# PM12_LDO.net
KiCad netlist of a schematic drawn in Altium Designer
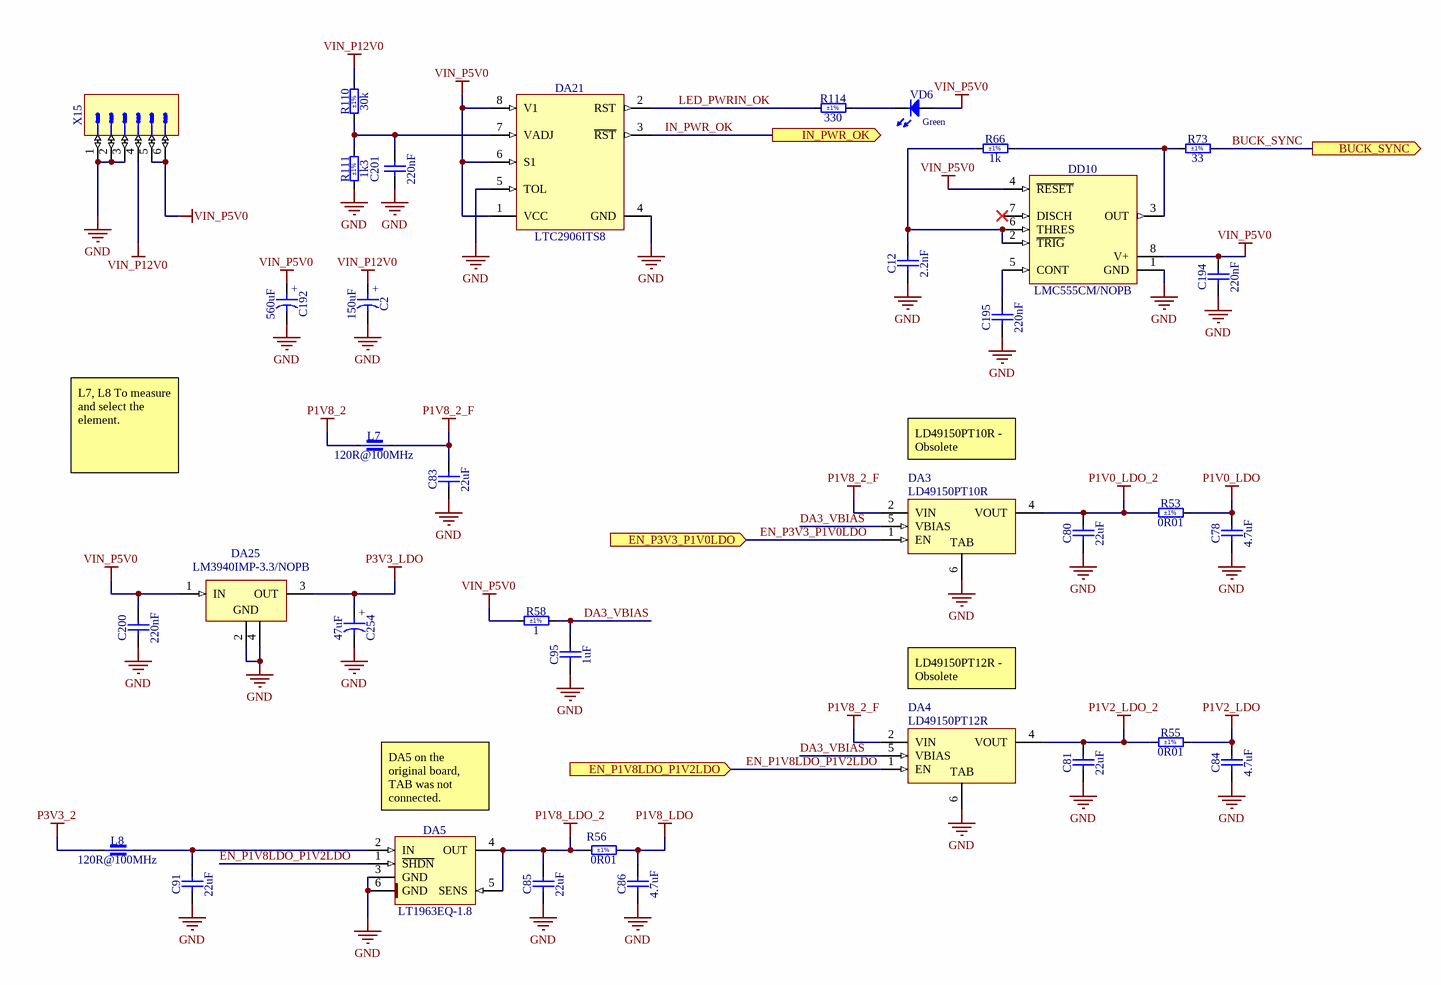
[diagram p0: PM12_LDO.SchDoc]

(export (version "E")
  (design (tool "Eeschema 10.0.6"))
  (components
    (comp (ref "C2")
      (value "150uF")
      (footprint "CAPAE830X1020N")
      (description "Polarised capacitor")
      (fields
        (field (name "PART NUMBER") "CAE830-1020_150UF_25V_20%")
        (field (name "VOLTAGE") "25V")
        (field (name "AUTHOR") "CERN DEM HF")
      )
      (libsource (lib "Capacitors") (part "Capacitor - polarized"))
    )
    (comp (ref "C12")
      (value "2.2nF")
      (footprint "CAPC2013X100N")
      (description "Non-polarised capacitor")
      (fields
        (field (name "PART NUMBER") "CC0805_2.2NF_50V_5%_C0G")
        (field (name "VOLTAGE") "50V")
        (field (name "AUTHOR") "CERN DEM MR")
      )
      (libsource (lib "Capacitors") (part "Capacitor - non polarized"))
    )
    (comp (ref "C78")
      (value "4.7uF")
      (footprint "CAPC2012X145N")
      (description "Non-polarised capacitor")
      (fields
        (field (name "PART NUMBER") "CC0805_4.7UF_50V_10%_X7R")
        (field (name "VOLTAGE") "50V")
        (field (name "AUTHOR") "CERN DEM JMW")
      )
      (libsource (lib "Capacitors") (part "Capacitor - non polarized"))
    )
    (comp (ref "C80")
      (value "22uF")
      (footprint "CAPC3216X180N")
      (description "Non-polarised capacitor")
      (fields
        (field (name "PART NUMBER") "CC1206_22UF_25V_20%_X5R")
        (field (name "VOLTAGE") "25V")
        (field (name "AUTHOR") "CERN DEM WB")
      )
      (libsource (lib "Capacitors") (part "Capacitor - non polarized"))
    )
    (comp (ref "C81")
      (value "22uF")
      (footprint "CAPC3216X180N")
      (description "Non-polarised capacitor")
      (fields
        (field (name "PART NUMBER") "CC1206_22UF_25V_20%_X5R")
        (field (name "VOLTAGE") "25V")
        (field (name "AUTHOR") "CERN DEM WB")
      )
      (libsource (lib "Capacitors") (part "Capacitor - non polarized"))
    )
    (comp (ref "C83")
      (value "22uF")
      (footprint "CAPC3216X180N")
      (description "Non-polarised capacitor")
      (fields
        (field (name "PART NUMBER") "CC1206_22UF_25V_20%_X5R")
        (field (name "VOLTAGE") "25V")
        (field (name "AUTHOR") "CERN DEM WB")
      )
      (libsource (lib "Capacitors") (part "Capacitor - non polarized"))
    )
    (comp (ref "C84")
      (value "4.7uF")
      (footprint "CAPC2012X145N")
      (description "Non-polarised capacitor")
      (fields
        (field (name "PART NUMBER") "CC0805_4.7UF_50V_10%_X7R")
        (field (name "VOLTAGE") "50V")
        (field (name "AUTHOR") "CERN DEM JMW")
      )
      (libsource (lib "Capacitors") (part "Capacitor - non polarized"))
    )
    (comp (ref "C85")
      (value "22uF")
      (footprint "CAPC3216X180N")
      (description "Non-polarised capacitor")
      (fields
        (field (name "PART NUMBER") "CC1206_22UF_25V_20%_X5R")
        (field (name "VOLTAGE") "25V")
        (field (name "AUTHOR") "CERN DEM WB")
      )
      (libsource (lib "Capacitors") (part "Capacitor - non polarized"))
    )
    (comp (ref "C86")
      (value "4.7uF")
      (footprint "CAPC2012X145N")
      (description "Non-polarised capacitor")
      (fields
        (field (name "PART NUMBER") "CC0805_4.7UF_50V_10%_X7R")
        (field (name "VOLTAGE") "50V")
        (field (name "AUTHOR") "CERN DEM JMW")
      )
      (libsource (lib "Capacitors") (part "Capacitor - non polarized"))
    )
    (comp (ref "C91")
      (value "22uF")
      (footprint "CAPC3216X180N")
      (description "Non-polarised capacitor")
      (fields
        (field (name "PART NUMBER") "CC1206_22UF_25V_20%_X5R")
        (field (name "VOLTAGE") "25V")
        (field (name "AUTHOR") "CERN DEM WB")
      )
      (libsource (lib "Capacitors") (part "Capacitor - non polarized"))
    )
    (comp (ref "C95")
      (value "1uF")
      (footprint "CAPC2012X140N")
      (description "Non-polarised capacitor")
      (fields
        (field (name "PART NUMBER") "CC0805_1UF_25V_10%_X7R")
        (field (name "VOLTAGE") "25V")
        (field (name "AUTHOR") "CERN DEM JLC")
      )
      (libsource (lib "Capacitors") (part "Capacitor - non polarized"))
    )
    (comp (ref "C192")
      (value "560uF")
      (footprint "CAPAE830X1020N")
      (description "Polarised capacitor")
      (fields
        (field (name "PART NUMBER") "CAE830-1020_560UF_10V_20%")
        (field (name "VOLTAGE") "10V")
        (field (name "AUTHOR") "CERN DEM HF")
      )
      (libsource (lib "Capacitors") (part "Capacitor - polarized"))
    )
    (comp (ref "C194")
      (value "220nF")
      (footprint "CAPC2012X135N")
      (description "Non-polarised capacitor")
      (fields
        (field (name "PART NUMBER") "CC0805_220NF_50V_10%_X7R")
        (field (name "VOLTAGE") "50V")
        (field (name "AUTHOR") "CERN DEM JLC")
      )
      (libsource (lib "Capacitors") (part "Capacitor - non polarized"))
    )
    (comp (ref "C195")
      (value "220nF")
      (footprint "CAPC2012X135N")
      (description "Non-polarised capacitor")
      (fields
        (field (name "PART NUMBER") "CC0805_220NF_50V_10%_X7R")
        (field (name "VOLTAGE") "50V")
        (field (name "AUTHOR") "CERN DEM JLC")
      )
      (libsource (lib "Capacitors") (part "Capacitor - non polarized"))
    )
    (comp (ref "C200")
      (value "220nF")
      (footprint "CAPC2012X135N")
      (description "Non-polarised capacitor")
      (fields
        (field (name "PART NUMBER") "CC0805_220NF_50V_10%_X7R")
        (field (name "VOLTAGE") "50V")
        (field (name "AUTHOR") "CERN DEM JLC")
      )
      (libsource (lib "Capacitors") (part "Capacitor - non polarized"))
    )
    (comp (ref "C201")
      (value "220nF")
      (footprint "CAPC2012X135N")
      (description "Non-polarised capacitor")
      (fields
        (field (name "PART NUMBER") "CC0805_220NF_50V_10%_X7R")
        (field (name "VOLTAGE") "50V")
        (field (name "AUTHOR") "CERN DEM JLC")
      )
      (libsource (lib "Capacitors") (part "Capacitor - non polarized"))
    )
    (comp (ref "C254")
      (value "47uF")
      (footprint "CAPAE530X610N")
      (description "Polarised capacitor")
      (fields
        (field (name "PART NUMBER") "CAE530-610_47UF_16V_20%")
        (field (name "VOLTAGE") "16V")
        (field (name "AUTHOR") "CERN DEM HF")
      )
      (libsource (lib "Capacitors") (part "Capacitor - polarized"))
    )
    (comp (ref "DA3")
      (value "LD49150PT10R")
      (footprint "PPAK_N")
      (description "1.5 Very Low Drop Voltage Regulator, 1.0V, 5-Pin PPAK, Tape and Reel")
      (libsource (lib "Altium Content Vault") (part "PM-REG-LD49300-SOT5"))
    )
    (comp (ref "DA4")
      (value "LD49150PT12R")
      (footprint "PPAK_M")
      (description "1.5 Very Low Drop Voltage Regulator, 1.2V, 5-Pin PPAK, Tape and Reel")
      (libsource (lib "Altium Content Vault") (part "PM-REG-LD49300-SOT5"))
    )
    (comp (ref "DA5")
      (value "LT1963EQ-1.8")
      (footprint "TO170P1394X457-6N-R900X1060")
      (description "1.5A, Fast Transient Response LDO Regulators")
      (fields (field (name "MANUFACTURER") "ANALOG DEVICES") (field (name "AUTHOR") "CERN DEM HF"))
      (libsource (lib "ICs And Semiconductors") (part "LT1963EQ-X"))
    )
    (comp (ref "DA21")
      (value "LTC2906ITS8")
      (footprint "SOT65P280X100-8N")
      (description "Precision Dual Supply Monitors with One Pin-Selectable Threshold and One Adjustable Input")
      (fields (field (name "MANUFACTURER") "LINEAR TECHNOLOGY") (field (name "AUTHOR") "CERN DEM HF"))
      (libsource (lib "ICs And Semiconductors") (part "LTC2906xTS8"))
    )
    (comp (ref "DA25")
      (value "LM3940IMP-3.3/NOPB")
      (footprint "SOT230P700X180-4N")
      (description "3-Terminal Regulator 1=IN 2=GND 3=OUT 4=GND")
      (fields
        (field (name "MANUFACTURER") "TEXAS INSTRUMENTS")
        (field (name "MANUFACTURER PART NUMBER") "LM3940IMP-3.3")
        (field (name "AUTHOR") "CERN DEM JLC")
      )
      (libsource (lib "ICs And Semiconductors") (part "REG3+1 1IN-2GND-3OUT+4GND"))
    )
    (comp (ref "DD10")
      (value "LMC555CM/NOPB")
      (footprint "SOIC127P600X175-8N")
      (description "CMOS Timer")
      (fields
        (field (name "MANUFACTURER") "NATIONAL SEMICONDUCTOR")
        (field (name "MANUFACTURER PART NUMBER") "LMC555CM")
        (field (name "AUTHOR") "CERN DEM JLC")
      )
      (libsource (lib "ICs And Semiconductors") (part "LMC555CM"))
    )
    (comp (ref "L7")
      (value "120R@100MHz")
      (footprint "IND_MURATA_BLM31KN")
      (fields
        (field (name "PART NUMBER") "IND1206_MURATA_BLM31KN121SN1")
        (field (name "POWER") "6A")
        (field (name "TOLERANCE") "±25%")
        (field (name "AUTHOR") "CERN DEM HF")
      )
      (libsource (lib "Inductors & Transformers") (part "Ferrite Bead"))
    )
    (comp (ref "L8")
      (value "120R@100MHz")
      (footprint "IND_MURATA_BLM31KN")
      (fields
        (field (name "PART NUMBER") "IND1206_MURATA_BLM31KN121SN1")
        (field (name "POWER") "6A")
        (field (name "TOLERANCE") "±25%")
        (field (name "AUTHOR") "CERN DEM HF")
      )
      (libsource (lib "Inductors & Transformers") (part "Ferrite Bead"))
    )
    (comp (ref "R53")
      (value "0R01")
      (footprint "RESC3216X80N")
      (description "Resistor - 1%")
      (fields
        (field (name "TOLERANCE") "±1%")
        (field (name "PART NUMBER") "R1206_0R01_1%_1W_100PPM_TT_LRMAM1206")
        (field (name "POWER") "1W")
        (field (name "AUTHOR") "CERN DEM BC")
      )
      (libsource (lib "Resistors") (part "Resistor - 1%"))
    )
    (comp (ref "R55")
      (value "0R01")
      (footprint "RESC3216X80N")
      (description "Resistor - 1%")
      (fields
        (field (name "TOLERANCE") "±1%")
        (field (name "PART NUMBER") "R1206_0R01_1%_1W_100PPM_TT_LRMAM1206")
        (field (name "POWER") "1W")
        (field (name "AUTHOR") "CERN DEM BC")
      )
      (libsource (lib "Resistors") (part "Resistor - 1%"))
    )
    (comp (ref "R56")
      (value "0R01")
      (footprint "RESC3216X80N")
      (description "Resistor - 1%")
      (fields
        (field (name "TOLERANCE") "±1%")
        (field (name "PART NUMBER") "R1206_0R01_1%_1W_100PPM_TT_LRMAM1206")
        (field (name "POWER") "1W")
        (field (name "AUTHOR") "CERN DEM BC")
      )
      (libsource (lib "Resistors") (part "Resistor - 1%"))
    )
    (comp (ref "R58")
      (value "1")
      (footprint "RESC2012X60N")
      (description "Resistor - 1%")
      (fields
        (field (name "TOLERANCE") "±1%")
        (field (name "PART NUMBER") "R0805_1R_1%_0.125W_100PPM")
        (field (name "POWER") "0.125W")
        (field (name "AUTHOR") "CERN DEM HF")
      )
      (libsource (lib "Resistors") (part "Resistor - 1%"))
    )
    (comp (ref "R66")
      (value "1k")
      (footprint "RESC2012X60N")
      (description "Resistor - 1%")
      (fields
        (field (name "TOLERANCE") "±1%")
        (field (name "PART NUMBER") "R0805_1K_1%_0.125W_100PPM")
        (field (name "POWER") "0.125W")
        (field (name "AUTHOR") "CERN DEM JLC")
      )
      (libsource (lib "Resistors") (part "Resistor - 1%"))
    )
    (comp (ref "R73")
      (value "33")
      (footprint "RESC2012X60N")
      (description "Resistor - 1%")
      (fields
        (field (name "TOLERANCE") "±1%")
        (field (name "PART NUMBER") "R0805_33R_1%_0.125W_100PPM")
        (field (name "POWER") "0.125W")
        (field (name "AUTHOR") "CERN DEM JLC")
      )
      (libsource (lib "Resistors") (part "Resistor - 1%"))
    )
    (comp (ref "R110")
      (value "30k")
      (footprint "RESC2012X60N")
      (description "Resistor - 1%")
      (fields
        (field (name "TOLERANCE") "±1%")
        (field (name "PART NUMBER") "R0805_30K_1%_0.125W_100PPM")
        (field (name "POWER") "0.125W")
        (field (name "AUTHOR") "CERN DEM JLC")
      )
      (libsource (lib "Resistors") (part "Resistor - 1%"))
    )
    (comp (ref "R111")
      (value "1k3")
      (footprint "RESC2012X60N")
      (description "Resistor - 1%")
      (fields
        (field (name "TOLERANCE") "±1%")
        (field (name "PART NUMBER") "R0805_1K3_1%_0.125W_100PPM")
        (field (name "POWER") "0.125W")
        (field (name "AUTHOR") "CERN DEM JLC")
      )
      (libsource (lib "Resistors") (part "Resistor - 1%"))
    )
    (comp (ref "R114")
      (value "330")
      (footprint "RESC2012X60N")
      (description "Resistor - 1%")
      (fields
        (field (name "TOLERANCE") "±1%")
        (field (name "PART NUMBER") "R0805_330R_1%_0.125W_100PPM")
        (field (name "POWER") "0.125W")
        (field (name "AUTHOR") "CERN DEM JLC")
      )
      (libsource (lib "Resistors") (part "Resistor - 1%"))
    )
    (comp (ref "VD6")
      (value "Green")
      (footprint "LED_KINGBRIGHT_KP-2012LSGC")
      (description "LED Green 1C 2A")
      (fields
        (field (name "PART NUMBER") "LED_KINGBRIGHT_KP-2012LSGC")
        (field (name "MANUFACTURER") "KINGBRIGHT")
        (field (name "AUTHOR") "CERN DEM BC")
      )
      (libsource (lib "ICs And Semiconductors") (part "LED Green 1C 2A"))
    )
    (comp (ref "X15")
      (value "Mini-Fit BMI")
      (footprint "MOLEX_15-24-9067")
      (description "Connector 6 Male")
      (fields
        (field (name "PART NUMBER") "MOLEX_15-24-9067")
        (field (name "MANUFACTURER") "MOLEX")
        (field (name "AUTHOR") "CERN DEM HF")
      )
      (libsource (lib "Connectors") (part "Connector 6 Male"))
    )
  )
  (nets
    (net (code "1") (name "/BUCK_SYNC") (class "Default")
      (node (ref "R73") (pin "2") (pinfunction "2_2") (pintype "passive"))
    )
    (net (code "2") (name "/DA3_VBIAS") (class "Default")
      (node (ref "C95") (pin "2") (pinfunction "2_2") (pintype "passive"))
      (node (ref "DA3") (pin "5") (pinfunction "VBIAS_5") (pintype "input"))
      (node (ref "DA4") (pin "5") (pinfunction "VBIAS_5") (pintype "input"))
      (node (ref "R58") (pin "2") (pinfunction "2_2") (pintype "passive"))
    )
    (net (code "3") (name "/EN_P1V8LDO_P1V2LDO") (class "Default")
      (node (ref "DA4") (pin "1") (pinfunction "EN_1") (pintype "input"))
      (node (ref "DA5") (pin "1") (pinfunction "~{SHDN}_1") (pintype "input"))
    )
    (net (code "4") (name "/EN_P3V3_P1V0LDO") (class "Default")
      (node (ref "DA3") (pin "1") (pinfunction "EN_1") (pintype "input"))
    )
    (net (code "5") (name "/IN_PWR_OK") (class "Default")
      (node (ref "DA21") (pin "3") (pinfunction "~{RST}_3") (pintype "output"))
    )
    (net (code "6") (name "/LED_PWRIN_OK") (class "Default")
      (node (ref "DA21") (pin "2") (pinfunction "RST_2") (pintype "output"))
      (node (ref "R114") (pin "1") (pinfunction "1_1") (pintype "passive"))
    )
    (net (code "7") (name "GND") (class "Default")
      (node (ref "C12") (pin "1") (pinfunction "1_1") (pintype "passive"))
      (node (ref "C192") (pin "2") (pinfunction "2_2") (pintype "passive"))
      (node (ref "C194") (pin "1") (pinfunction "1_1") (pintype "passive"))
      (node (ref "C195") (pin "1") (pinfunction "1_1") (pintype "passive"))
      (node (ref "C2") (pin "2") (pinfunction "2_2") (pintype "passive"))
      (node (ref "C200") (pin "1") (pinfunction "1_1") (pintype "passive"))
      (node (ref "C201") (pin "1") (pinfunction "1_1") (pintype "passive"))
      (node (ref "C254") (pin "2") (pinfunction "2_2") (pintype "passive"))
      (node (ref "C78") (pin "1") (pinfunction "1_1") (pintype "passive"))
      (node (ref "C80") (pin "1") (pinfunction "1_1") (pintype "passive"))
      (node (ref "C81") (pin "1") (pinfunction "1_1") (pintype "passive"))
      (node (ref "C83") (pin "1") (pinfunction "1_1") (pintype "passive"))
      (node (ref "C84") (pin "1") (pinfunction "1_1") (pintype "passive"))
      (node (ref "C85") (pin "1") (pinfunction "1_1") (pintype "passive"))
      (node (ref "C86") (pin "1") (pinfunction "1_1") (pintype "passive"))
      (node (ref "C91") (pin "1") (pinfunction "1_1") (pintype "passive"))
      (node (ref "C95") (pin "1") (pinfunction "1_1") (pintype "passive"))
      (node (ref "DA21") (pin "4") (pinfunction "GND_4") (pintype "power_in"))
      (node (ref "DA21") (pin "5") (pinfunction "TOL_5") (pintype "input"))
      (node (ref "DA25") (pin "2") (pinfunction "GND_2") (pintype "power_in"))
      (node (ref "DA25") (pin "4") (pinfunction "GND_4") (pintype "power_in"))
      (node (ref "DA3") (pin "6") (pinfunction "TAB_6") (pintype "power_in"))
      (node (ref "DA4") (pin "6") (pinfunction "TAB_6") (pintype "power_in"))
      (node (ref "DA5") (pin "3") (pinfunction "GND_3") (pintype "power_in"))
      (node (ref "DA5") (pin "6") (pinfunction "GND_6") (pintype "power_in"))
      (node (ref "DD10") (pin "1") (pinfunction "GND_1") (pintype "power_in"))
      (node (ref "R111") (pin "1") (pinfunction "1_1") (pintype "passive"))
      (node (ref "X15") (pin "1") (pinfunction "1_1") (pintype "bidirectional"))
      (node (ref "X15") (pin "2") (pinfunction "2_2") (pintype "bidirectional"))
      (node (ref "X15") (pin "3") (pinfunction "3_3") (pintype "bidirectional"))
    )
    (net (code "8") (name "Net-(DA5-IN)") (class "Default")
      (node (ref "C91") (pin "2") (pinfunction "2_2") (pintype "passive"))
      (node (ref "DA5") (pin "2") (pinfunction "IN_2") (pintype "input"))
      (node (ref "L8") (pin "2") (pinfunction "2_2") (pintype "passive"))
    )
    (net (code "9") (name "Net-(DA21-VADJ)") (class "Default")
      (node (ref "C201") (pin "2") (pinfunction "2_2") (pintype "passive"))
      (node (ref "DA21") (pin "7") (pinfunction "VADJ_7") (pintype "input"))
      (node (ref "R110") (pin "1") (pinfunction "1_1") (pintype "passive"))
      (node (ref "R111") (pin "2") (pinfunction "2_2") (pintype "passive"))
    )
    (net (code "10") (name "Net-(DD10-CONT)") (class "Default")
      (node (ref "C195") (pin "2") (pinfunction "2_2") (pintype "passive"))
      (node (ref "DD10") (pin "5") (pinfunction "CONT_5") (pintype "input"))
    )
    (net (code "11") (name "Net-(DD10-OUT)") (class "Default")
      (node (ref "DD10") (pin "3") (pinfunction "OUT_3") (pintype "output"))
      (node (ref "R66") (pin "2") (pinfunction "2_2") (pintype "passive"))
      (node (ref "R73") (pin "1") (pinfunction "1_1") (pintype "passive"))
    )
    (net (code "12") (name "Net-(DD10-THRES)") (class "Default")
      (node (ref "C12") (pin "2") (pinfunction "2_2") (pintype "passive"))
      (node (ref "DD10") (pin "2") (pinfunction "~{TRIG}_2") (pintype "input"))
      (node (ref "DD10") (pin "6") (pinfunction "THRES_6") (pintype "input"))
      (node (ref "R66") (pin "1") (pinfunction "1_1") (pintype "passive"))
    )
    (net (code "13") (name "Net-(VD6-C)") (class "Default")
      (node (ref "R114") (pin "2") (pinfunction "2_2") (pintype "passive"))
      (node (ref "VD6") (pin "1") (pinfunction "C_1") (pintype "passive"))
    )
    (net (code "14") (name "P1V0_LDO") (class "Default")
      (node (ref "C78") (pin "2") (pinfunction "2_2") (pintype "passive"))
      (node (ref "R53") (pin "2") (pinfunction "2_2") (pintype "passive"))
    )
    (net (code "15") (name "P1V0_LDO_2") (class "Default")
      (node (ref "C80") (pin "2") (pinfunction "2_2") (pintype "passive"))
      (node (ref "DA3") (pin "4") (pinfunction "VOUT_4") (pintype "power_in"))
      (node (ref "R53") (pin "1") (pinfunction "1_1") (pintype "passive"))
    )
    (net (code "16") (name "P1V2_LDO") (class "Default")
      (node (ref "C84") (pin "2") (pinfunction "2_2") (pintype "passive"))
      (node (ref "R55") (pin "2") (pinfunction "2_2") (pintype "passive"))
    )
    (net (code "17") (name "P1V2_LDO_2") (class "Default")
      (node (ref "C81") (pin "2") (pinfunction "2_2") (pintype "passive"))
      (node (ref "DA4") (pin "4") (pinfunction "VOUT_4") (pintype "power_in"))
      (node (ref "R55") (pin "1") (pinfunction "1_1") (pintype "passive"))
    )
    (net (code "18") (name "P1V8_2") (class "Default")
      (node (ref "L7") (pin "1") (pinfunction "1_1") (pintype "passive"))
    )
    (net (code "19") (name "P1V8_2_F") (class "Default")
      (node (ref "C83") (pin "2") (pinfunction "2_2") (pintype "passive"))
      (node (ref "DA3") (pin "2") (pinfunction "VIN_2") (pintype "power_in"))
      (node (ref "DA4") (pin "2") (pinfunction "VIN_2") (pintype "power_in"))
      (node (ref "L7") (pin "2") (pinfunction "2_2") (pintype "passive"))
    )
    (net (code "20") (name "P1V8_LDO") (class "Default")
      (node (ref "C86") (pin "2") (pinfunction "2_2") (pintype "passive"))
      (node (ref "R56") (pin "2") (pinfunction "2_2") (pintype "passive"))
    )
    (net (code "21") (name "P1V8_LDO_2") (class "Default")
      (node (ref "C85") (pin "2") (pinfunction "2_2") (pintype "passive"))
      (node (ref "DA5") (pin "4") (pinfunction "OUT_4") (pintype "power_in"))
      (node (ref "DA5") (pin "5") (pinfunction "SENS_5") (pintype "input"))
      (node (ref "R56") (pin "1") (pinfunction "1_1") (pintype "passive"))
    )
    (net (code "22") (name "P3V3_2") (class "Default")
      (node (ref "L8") (pin "1") (pinfunction "1_1") (pintype "passive"))
    )
    (net (code "23") (name "P3V3_LDO") (class "Default")
      (node (ref "C254") (pin "1") (pinfunction "1_1") (pintype "passive"))
      (node (ref "DA25") (pin "3") (pinfunction "OUT_3") (pintype "power_in"))
    )
    (net (code "24") (name "VIN_P5V0") (class "Default")
      (node (ref "C192") (pin "1") (pinfunction "1_1") (pintype "passive"))
      (node (ref "C194") (pin "2") (pinfunction "2_2") (pintype "passive"))
      (node (ref "C200") (pin "2") (pinfunction "2_2") (pintype "passive"))
      (node (ref "DA21") (pin "1") (pinfunction "VCC_1") (pintype "power_in"))
      (node (ref "DA21") (pin "6") (pinfunction "S1_6") (pintype "input"))
      (node (ref "DA21") (pin "8") (pinfunction "V1_8") (pintype "input"))
      (node (ref "DA25") (pin "1") (pinfunction "IN_1") (pintype "input"))
      (node (ref "DD10") (pin "4") (pinfunction "~{RESET}_4") (pintype "input"))
      (node (ref "DD10") (pin "8") (pinfunction "V+_8") (pintype "power_in"))
      (node (ref "R58") (pin "1") (pinfunction "1_1") (pintype "passive"))
      (node (ref "VD6") (pin "2") (pinfunction "A_2") (pintype "passive"))
      (node (ref "X15") (pin "5") (pinfunction "5_5") (pintype "bidirectional"))
      (node (ref "X15") (pin "6") (pinfunction "6_6") (pintype "bidirectional"))
    )
    (net (code "25") (name "VIN_P12V0") (class "Default")
      (node (ref "C2") (pin "1") (pinfunction "1_1") (pintype "passive"))
      (node (ref "R110") (pin "2") (pinfunction "2_2") (pintype "passive"))
      (node (ref "X15") (pin "4") (pinfunction "4_4") (pintype "bidirectional"))
    )
    (net (code "26") (name "unconnected-(DD10-DISCH-Pad7)") (class "Default")
      (node (ref "DD10") (pin "7") (pinfunction "DISCH_7") (pintype "input+no_connect"))
    )
  )
)
